# Distribution_board.net
KiCad netlist of a schematic drawn in EAGLE
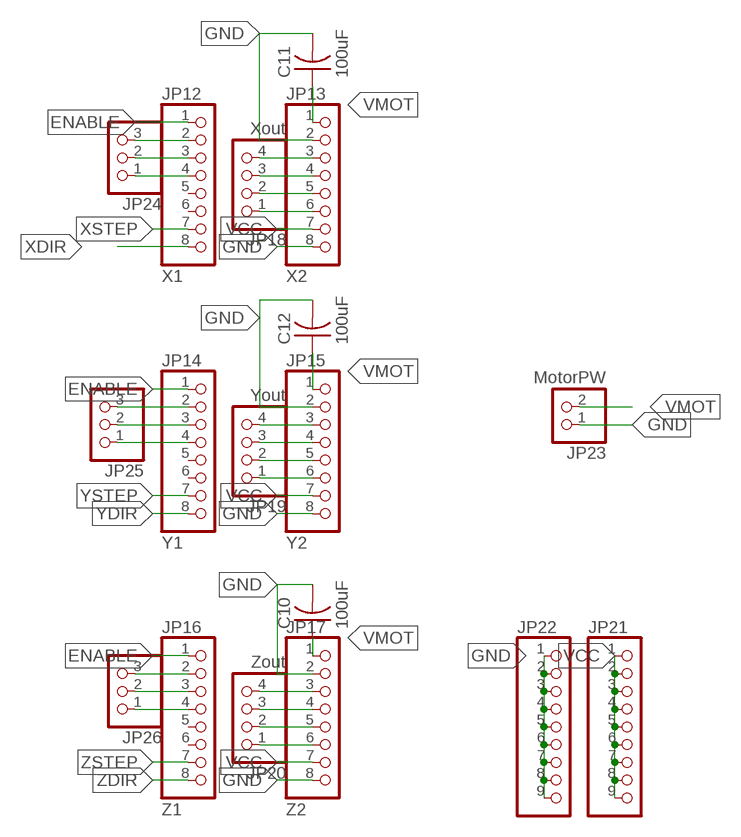
[diagram p0: schematic, sheet 1]

(export (version "E")
  (design (tool "Eeschema 10.0.6"))
  (components
    (comp (ref "C10")
      (value "100uF")
      (footprint "eagle-import:C1206")
      (libsource (lib "eagle-import") (part "CAP-US1206"))
    )
    (comp (ref "C11")
      (value "100uF")
      (footprint "eagle-import:C1206")
      (libsource (lib "eagle-import") (part "CAP-US1206"))
    )
    (comp (ref "C12")
      (value "100uF")
      (footprint "eagle-import:C1206")
      (libsource (lib "eagle-import") (part "CAP-US1206"))
    )
    (comp (ref "JP12")
      (value "X1")
      (footprint "eagle-import:1X08")
      (libsource (lib "eagle-import") (part "PINHD-1X8"))
    )
    (comp (ref "JP13")
      (value "X2")
      (footprint "eagle-import:1X08")
      (libsource (lib "eagle-import") (part "PINHD-1X8"))
    )
    (comp (ref "JP14")
      (value "Y1")
      (footprint "eagle-import:1X08")
      (libsource (lib "eagle-import") (part "PINHD-1X8"))
    )
    (comp (ref "JP15")
      (value "Y2")
      (footprint "eagle-import:1X08")
      (libsource (lib "eagle-import") (part "PINHD-1X8"))
    )
    (comp (ref "JP16")
      (value "Z1")
      (footprint "eagle-import:1X08")
      (libsource (lib "eagle-import") (part "PINHD-1X8"))
    )
    (comp (ref "JP17")
      (value "Z2")
      (footprint "eagle-import:1X08")
      (libsource (lib "eagle-import") (part "PINHD-1X8"))
    )
    (comp (ref "JP18")
      (value "Xout")
      (footprint "eagle-import:1X04")
      (libsource (lib "eagle-import") (part "PINHD-1X4"))
    )
    (comp (ref "JP19")
      (value "Yout")
      (footprint "eagle-import:1X04")
      (libsource (lib "eagle-import") (part "PINHD-1X4"))
    )
    (comp (ref "JP20")
      (value "Zout")
      (footprint "eagle-import:1X04")
      (libsource (lib "eagle-import") (part "PINHD-1X4"))
    )
    (comp (ref "JP21")
      (value "PINHD-1X9")
      (footprint "eagle-import:1X09")
      (libsource (lib "eagle-import") (part "PINHD-1X9"))
    )
    (comp (ref "JP22")
      (value "PINHD-1X9")
      (footprint "eagle-import:1X09")
      (libsource (lib "eagle-import") (part "PINHD-1X9"))
    )
    (comp (ref "JP23")
      (value "MotorPW")
      (footprint "eagle-import:1X02")
      (libsource (lib "eagle-import") (part "PINHD-1X2"))
    )
    (comp (ref "JP24")
      (value "PINHD-1X3")
      (footprint "eagle-import:1X03")
      (libsource (lib "eagle-import") (part "PINHD-1X3"))
    )
    (comp (ref "JP25")
      (value "PINHD-1X3")
      (footprint "eagle-import:1X03")
      (libsource (lib "eagle-import") (part "PINHD-1X3"))
    )
    (comp (ref "JP26")
      (value "PINHD-1X3")
      (footprint "eagle-import:1X03")
      (libsource (lib "eagle-import") (part "PINHD-1X3"))
    )
  )
  (nets
    (net (code "1") (name "ENABLE") (class "Default")
      (node (ref "JP12") (pin "1") (pinfunction "1_1") (pintype "passive"))
      (node (ref "JP14") (pin "1") (pinfunction "1_1") (pintype "passive"))
      (node (ref "JP16") (pin "1") (pinfunction "1_1") (pintype "passive"))
    )
    (net (code "2") (name "GND") (class "Default")
      (node (ref "C10") (pin "2") (pinfunction "2_2") (pintype "passive"))
      (node (ref "C11") (pin "2") (pinfunction "2_2") (pintype "passive"))
      (node (ref "C12") (pin "2") (pinfunction "2_2") (pintype "passive"))
      (node (ref "JP13") (pin "2") (pinfunction "2_2") (pintype "passive"))
      (node (ref "JP13") (pin "8") (pinfunction "8_8") (pintype "passive"))
      (node (ref "JP15") (pin "2") (pinfunction "2_2") (pintype "passive"))
      (node (ref "JP15") (pin "8") (pinfunction "8_8") (pintype "passive"))
      (node (ref "JP17") (pin "2") (pinfunction "2_2") (pintype "passive"))
      (node (ref "JP17") (pin "8") (pinfunction "8_8") (pintype "passive"))
      (node (ref "JP22") (pin "1") (pinfunction "1_1") (pintype "passive"))
      (node (ref "JP22") (pin "2") (pinfunction "2_2") (pintype "passive"))
      (node (ref "JP22") (pin "3") (pinfunction "3_3") (pintype "passive"))
      (node (ref "JP22") (pin "4") (pinfunction "4_4") (pintype "passive"))
      (node (ref "JP22") (pin "5") (pinfunction "5_5") (pintype "passive"))
      (node (ref "JP22") (pin "6") (pinfunction "6_6") (pintype "passive"))
      (node (ref "JP22") (pin "7") (pinfunction "7_7") (pintype "passive"))
      (node (ref "JP22") (pin "8") (pinfunction "8_8") (pintype "passive"))
      (node (ref "JP22") (pin "9") (pinfunction "9_9") (pintype "passive"))
      (node (ref "JP23") (pin "1") (pinfunction "1_1") (pintype "passive"))
    )
    (net (code "3") (name "Net-(JP12-Pad2)") (class "Default")
      (node (ref "JP12") (pin "2") (pinfunction "2_2") (pintype "passive"))
      (node (ref "JP24") (pin "3") (pinfunction "3_3") (pintype "passive"))
    )
    (net (code "4") (name "Net-(JP12-Pad3)") (class "Default")
      (node (ref "JP12") (pin "3") (pinfunction "3_3") (pintype "passive"))
      (node (ref "JP24") (pin "2") (pinfunction "2_2") (pintype "passive"))
    )
    (net (code "5") (name "Net-(JP12-Pad4)") (class "Default")
      (node (ref "JP12") (pin "4") (pinfunction "4_4") (pintype "passive"))
      (node (ref "JP24") (pin "1") (pinfunction "1_1") (pintype "passive"))
    )
    (net (code "6") (name "Net-(JP13-Pad3)") (class "Default")
      (node (ref "JP13") (pin "3") (pinfunction "3_3") (pintype "passive"))
      (node (ref "JP18") (pin "4") (pinfunction "4_4") (pintype "passive"))
    )
    (net (code "7") (name "Net-(JP13-Pad4)") (class "Default")
      (node (ref "JP13") (pin "4") (pinfunction "4_4") (pintype "passive"))
      (node (ref "JP18") (pin "3") (pinfunction "3_3") (pintype "passive"))
    )
    (net (code "8") (name "Net-(JP13-Pad5)") (class "Default")
      (node (ref "JP13") (pin "5") (pinfunction "5_5") (pintype "passive"))
      (node (ref "JP18") (pin "2") (pinfunction "2_2") (pintype "passive"))
    )
    (net (code "9") (name "Net-(JP13-Pad6)") (class "Default")
      (node (ref "JP13") (pin "6") (pinfunction "6_6") (pintype "passive"))
      (node (ref "JP18") (pin "1") (pinfunction "1_1") (pintype "passive"))
    )
    (net (code "10") (name "Net-(JP14-Pad2)") (class "Default")
      (node (ref "JP14") (pin "2") (pinfunction "2_2") (pintype "passive"))
      (node (ref "JP25") (pin "3") (pinfunction "3_3") (pintype "passive"))
    )
    (net (code "11") (name "Net-(JP14-Pad3)") (class "Default")
      (node (ref "JP14") (pin "3") (pinfunction "3_3") (pintype "passive"))
      (node (ref "JP25") (pin "2") (pinfunction "2_2") (pintype "passive"))
    )
    (net (code "12") (name "Net-(JP14-Pad4)") (class "Default")
      (node (ref "JP14") (pin "4") (pinfunction "4_4") (pintype "passive"))
      (node (ref "JP25") (pin "1") (pinfunction "1_1") (pintype "passive"))
    )
    (net (code "13") (name "Net-(JP15-Pad3)") (class "Default")
      (node (ref "JP15") (pin "3") (pinfunction "3_3") (pintype "passive"))
      (node (ref "JP19") (pin "4") (pinfunction "4_4") (pintype "passive"))
    )
    (net (code "14") (name "Net-(JP15-Pad4)") (class "Default")
      (node (ref "JP15") (pin "4") (pinfunction "4_4") (pintype "passive"))
      (node (ref "JP19") (pin "3") (pinfunction "3_3") (pintype "passive"))
    )
    (net (code "15") (name "Net-(JP15-Pad5)") (class "Default")
      (node (ref "JP15") (pin "5") (pinfunction "5_5") (pintype "passive"))
      (node (ref "JP19") (pin "2") (pinfunction "2_2") (pintype "passive"))
    )
    (net (code "16") (name "Net-(JP15-Pad6)") (class "Default")
      (node (ref "JP15") (pin "6") (pinfunction "6_6") (pintype "passive"))
      (node (ref "JP19") (pin "1") (pinfunction "1_1") (pintype "passive"))
    )
    (net (code "17") (name "Net-(JP16-Pad2)") (class "Default")
      (node (ref "JP16") (pin "2") (pinfunction "2_2") (pintype "passive"))
      (node (ref "JP26") (pin "3") (pinfunction "3_3") (pintype "passive"))
    )
    (net (code "18") (name "Net-(JP16-Pad3)") (class "Default")
      (node (ref "JP16") (pin "3") (pinfunction "3_3") (pintype "passive"))
      (node (ref "JP26") (pin "2") (pinfunction "2_2") (pintype "passive"))
    )
    (net (code "19") (name "Net-(JP16-Pad4)") (class "Default")
      (node (ref "JP16") (pin "4") (pinfunction "4_4") (pintype "passive"))
      (node (ref "JP26") (pin "1") (pinfunction "1_1") (pintype "passive"))
    )
    (net (code "20") (name "Net-(JP17-Pad3)") (class "Default")
      (node (ref "JP17") (pin "3") (pinfunction "3_3") (pintype "passive"))
      (node (ref "JP20") (pin "4") (pinfunction "4_4") (pintype "passive"))
    )
    (net (code "21") (name "Net-(JP17-Pad4)") (class "Default")
      (node (ref "JP17") (pin "4") (pinfunction "4_4") (pintype "passive"))
      (node (ref "JP20") (pin "3") (pinfunction "3_3") (pintype "passive"))
    )
    (net (code "22") (name "Net-(JP17-Pad5)") (class "Default")
      (node (ref "JP17") (pin "5") (pinfunction "5_5") (pintype "passive"))
      (node (ref "JP20") (pin "2") (pinfunction "2_2") (pintype "passive"))
    )
    (net (code "23") (name "Net-(JP17-Pad6)") (class "Default")
      (node (ref "JP17") (pin "6") (pinfunction "6_6") (pintype "passive"))
      (node (ref "JP20") (pin "1") (pinfunction "1_1") (pintype "passive"))
    )
    (net (code "24") (name "VCC") (class "Default")
      (node (ref "JP13") (pin "7") (pinfunction "7_7") (pintype "passive"))
      (node (ref "JP15") (pin "7") (pinfunction "7_7") (pintype "passive"))
      (node (ref "JP17") (pin "7") (pinfunction "7_7") (pintype "passive"))
      (node (ref "JP21") (pin "1") (pinfunction "1_1") (pintype "passive"))
      (node (ref "JP21") (pin "2") (pinfunction "2_2") (pintype "passive"))
      (node (ref "JP21") (pin "3") (pinfunction "3_3") (pintype "passive"))
      (node (ref "JP21") (pin "4") (pinfunction "4_4") (pintype "passive"))
      (node (ref "JP21") (pin "5") (pinfunction "5_5") (pintype "passive"))
      (node (ref "JP21") (pin "6") (pinfunction "6_6") (pintype "passive"))
      (node (ref "JP21") (pin "7") (pinfunction "7_7") (pintype "passive"))
      (node (ref "JP21") (pin "8") (pinfunction "8_8") (pintype "passive"))
      (node (ref "JP21") (pin "9") (pinfunction "9_9") (pintype "passive"))
    )
    (net (code "25") (name "VMOT") (class "Default")
      (node (ref "C10") (pin "1") (pinfunction "1_1") (pintype "passive"))
      (node (ref "C11") (pin "1") (pinfunction "1_1") (pintype "passive"))
      (node (ref "C12") (pin "1") (pinfunction "1_1") (pintype "passive"))
      (node (ref "JP13") (pin "1") (pinfunction "1_1") (pintype "passive"))
      (node (ref "JP15") (pin "1") (pinfunction "1_1") (pintype "passive"))
      (node (ref "JP17") (pin "1") (pinfunction "1_1") (pintype "passive"))
      (node (ref "JP23") (pin "2") (pinfunction "2_2") (pintype "passive"))
    )
    (net (code "26") (name "XDIR") (class "Default")
      (node (ref "JP12") (pin "8") (pinfunction "8_8") (pintype "passive"))
    )
    (net (code "27") (name "XSTEP") (class "Default")
      (node (ref "JP12") (pin "7") (pinfunction "7_7") (pintype "passive"))
    )
    (net (code "28") (name "YDIR") (class "Default")
      (node (ref "JP14") (pin "8") (pinfunction "8_8") (pintype "passive"))
    )
    (net (code "29") (name "YSTEP") (class "Default")
      (node (ref "JP14") (pin "7") (pinfunction "7_7") (pintype "passive"))
    )
    (net (code "30") (name "ZDIR") (class "Default")
      (node (ref "JP16") (pin "8") (pinfunction "8_8") (pintype "passive"))
    )
    (net (code "31") (name "ZSTEP") (class "Default")
      (node (ref "JP16") (pin "7") (pinfunction "7_7") (pintype "passive"))
    )
    (net (code "32") (name "unconnected-(JP12-Pad5)") (class "Default")
      (node (ref "JP12") (pin "5") (pinfunction "5_5") (pintype "passive"))
    )
    (net (code "33") (name "unconnected-(JP12-Pad6)") (class "Default")
      (node (ref "JP12") (pin "6") (pinfunction "6_6") (pintype "passive"))
    )
    (net (code "34") (name "unconnected-(JP14-Pad5)") (class "Default")
      (node (ref "JP14") (pin "5") (pinfunction "5_5") (pintype "passive"))
    )
    (net (code "35") (name "unconnected-(JP14-Pad6)") (class "Default")
      (node (ref "JP14") (pin "6") (pinfunction "6_6") (pintype "passive"))
    )
    (net (code "36") (name "unconnected-(JP16-Pad5)") (class "Default")
      (node (ref "JP16") (pin "5") (pinfunction "5_5") (pintype "passive"))
    )
    (net (code "37") (name "unconnected-(JP16-Pad6)") (class "Default")
      (node (ref "JP16") (pin "6") (pinfunction "6_6") (pintype "passive"))
    )
  )
)
